# sa-22c-microsemi-connector-flip.net
KiCad netlist of a schematic drawn in EAGLE
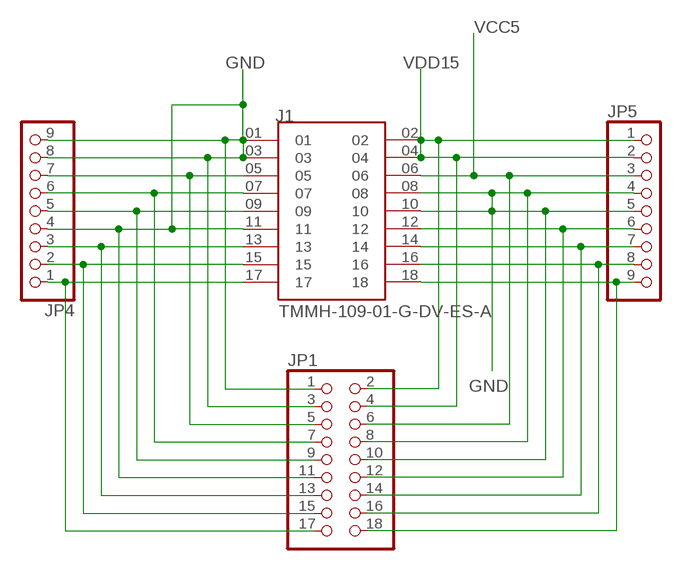
[diagram p0: schematic, sheet 1]

(export (version "E")
  (design (tool "Eeschema 10.0.6"))
  (components
    (comp (ref "J1")
      (value "TMMH-109-01-G-DV-ES-A")
      (footprint "eagle-import:SAMTEC_TMMH-109-01-G-DV-ES-A")
      (fields (field (name "MANUFACTURER") "Samtec"))
      (libsource (lib "eagle-import") (part "TMMH-109-01-G-DV-ES-A"))
    )
    (comp (ref "JP1")
      (value "PINHD-2X9")
      (footprint "eagle-import:2X09")
      (libsource (lib "eagle-import") (part "PINHD-2X9"))
    )
    (comp (ref "JP4")
      (value "PINHD-1X9")
      (footprint "eagle-import:1X09")
      (libsource (lib "eagle-import") (part "PINHD-1X9"))
    )
    (comp (ref "JP5")
      (value "PINHD-1X9")
      (footprint "eagle-import:1X09")
      (libsource (lib "eagle-import") (part "PINHD-1X9"))
    )
  )
  (nets
    (net (code "1") (name "/GND") (class "Default")
      (node (ref "J1") (pin "01") (pinfunction "01_01") (pintype "passive"))
      (node (ref "J1") (pin "03") (pinfunction "03_03") (pintype "passive"))
      (node (ref "J1") (pin "08") (pinfunction "08_08") (pintype "passive"))
      (node (ref "J1") (pin "10") (pinfunction "10_10") (pintype "passive"))
      (node (ref "J1") (pin "11") (pinfunction "11_11") (pintype "passive"))
      (node (ref "JP1") (pin "1") (pinfunction "1_1") (pintype "passive"))
      (node (ref "JP1") (pin "10") (pinfunction "10_10") (pintype "passive"))
      (node (ref "JP1") (pin "11") (pinfunction "11_11") (pintype "passive"))
      (node (ref "JP1") (pin "3") (pinfunction "3_3") (pintype "passive"))
      (node (ref "JP1") (pin "8") (pinfunction "8_8") (pintype "passive"))
      (node (ref "JP4") (pin "4") (pinfunction "4_4") (pintype "passive"))
      (node (ref "JP4") (pin "8") (pinfunction "8_8") (pintype "passive"))
      (node (ref "JP4") (pin "9") (pinfunction "9_9") (pintype "passive"))
      (node (ref "JP5") (pin "4") (pinfunction "4_4") (pintype "passive"))
      (node (ref "JP5") (pin "5") (pinfunction "5_5") (pintype "passive"))
    )
    (net (code "2") (name "/VCC5") (class "Default")
      (node (ref "J1") (pin "06") (pinfunction "06_06") (pintype "passive"))
      (node (ref "JP1") (pin "6") (pinfunction "6_6") (pintype "passive"))
      (node (ref "JP5") (pin "3") (pinfunction "3_3") (pintype "passive"))
    )
    (net (code "3") (name "/VDD15") (class "Default")
      (node (ref "J1") (pin "02") (pinfunction "02_02") (pintype "passive"))
      (node (ref "J1") (pin "04") (pinfunction "04_04") (pintype "passive"))
      (node (ref "JP1") (pin "2") (pinfunction "2_2") (pintype "passive"))
      (node (ref "JP1") (pin "4") (pinfunction "4_4") (pintype "passive"))
      (node (ref "JP5") (pin "1") (pinfunction "1_1") (pintype "passive"))
      (node (ref "JP5") (pin "2") (pinfunction "2_2") (pintype "passive"))
    )
    (net (code "4") (name "Net-(J1-Pad05)") (class "Default")
      (node (ref "J1") (pin "05") (pinfunction "05_05") (pintype "passive"))
      (node (ref "JP1") (pin "5") (pinfunction "5_5") (pintype "passive"))
      (node (ref "JP4") (pin "7") (pinfunction "7_7") (pintype "passive"))
    )
    (net (code "5") (name "Net-(J1-Pad07)") (class "Default")
      (node (ref "J1") (pin "07") (pinfunction "07_07") (pintype "passive"))
      (node (ref "JP1") (pin "7") (pinfunction "7_7") (pintype "passive"))
      (node (ref "JP4") (pin "6") (pinfunction "6_6") (pintype "passive"))
    )
    (net (code "6") (name "Net-(J1-Pad09)") (class "Default")
      (node (ref "J1") (pin "09") (pinfunction "09_09") (pintype "passive"))
      (node (ref "JP1") (pin "9") (pinfunction "9_9") (pintype "passive"))
      (node (ref "JP4") (pin "5") (pinfunction "5_5") (pintype "passive"))
    )
    (net (code "7") (name "Net-(J1-Pad12)") (class "Default")
      (node (ref "J1") (pin "12") (pinfunction "12_12") (pintype "passive"))
      (node (ref "JP1") (pin "12") (pinfunction "12_12") (pintype "passive"))
      (node (ref "JP5") (pin "6") (pinfunction "6_6") (pintype "passive"))
    )
    (net (code "8") (name "Net-(J1-Pad13)") (class "Default")
      (node (ref "J1") (pin "13") (pinfunction "13_13") (pintype "passive"))
      (node (ref "JP1") (pin "13") (pinfunction "13_13") (pintype "passive"))
      (node (ref "JP4") (pin "3") (pinfunction "3_3") (pintype "passive"))
    )
    (net (code "9") (name "Net-(J1-Pad14)") (class "Default")
      (node (ref "J1") (pin "14") (pinfunction "14_14") (pintype "passive"))
      (node (ref "JP1") (pin "14") (pinfunction "14_14") (pintype "passive"))
      (node (ref "JP5") (pin "7") (pinfunction "7_7") (pintype "passive"))
    )
    (net (code "10") (name "Net-(J1-Pad15)") (class "Default")
      (node (ref "J1") (pin "15") (pinfunction "15_15") (pintype "passive"))
      (node (ref "JP1") (pin "15") (pinfunction "15_15") (pintype "passive"))
      (node (ref "JP4") (pin "2") (pinfunction "2_2") (pintype "passive"))
    )
    (net (code "11") (name "Net-(J1-Pad16)") (class "Default")
      (node (ref "J1") (pin "16") (pinfunction "16_16") (pintype "passive"))
      (node (ref "JP1") (pin "16") (pinfunction "16_16") (pintype "passive"))
      (node (ref "JP5") (pin "8") (pinfunction "8_8") (pintype "passive"))
    )
    (net (code "12") (name "Net-(J1-Pad17)") (class "Default")
      (node (ref "J1") (pin "17") (pinfunction "17_17") (pintype "passive"))
      (node (ref "JP1") (pin "17") (pinfunction "17_17") (pintype "passive"))
      (node (ref "JP4") (pin "1") (pinfunction "1_1") (pintype "passive"))
    )
    (net (code "13") (name "Net-(J1-Pad18)") (class "Default")
      (node (ref "J1") (pin "18") (pinfunction "18_18") (pintype "passive"))
      (node (ref "JP1") (pin "18") (pinfunction "18_18") (pintype "passive"))
      (node (ref "JP5") (pin "9") (pinfunction "9_9") (pintype "passive"))
    )
  )
)
